# KegWasher_1_8_LogicIO_Schematic.net
KiCad netlist of a schematic drawn in EasyEDA
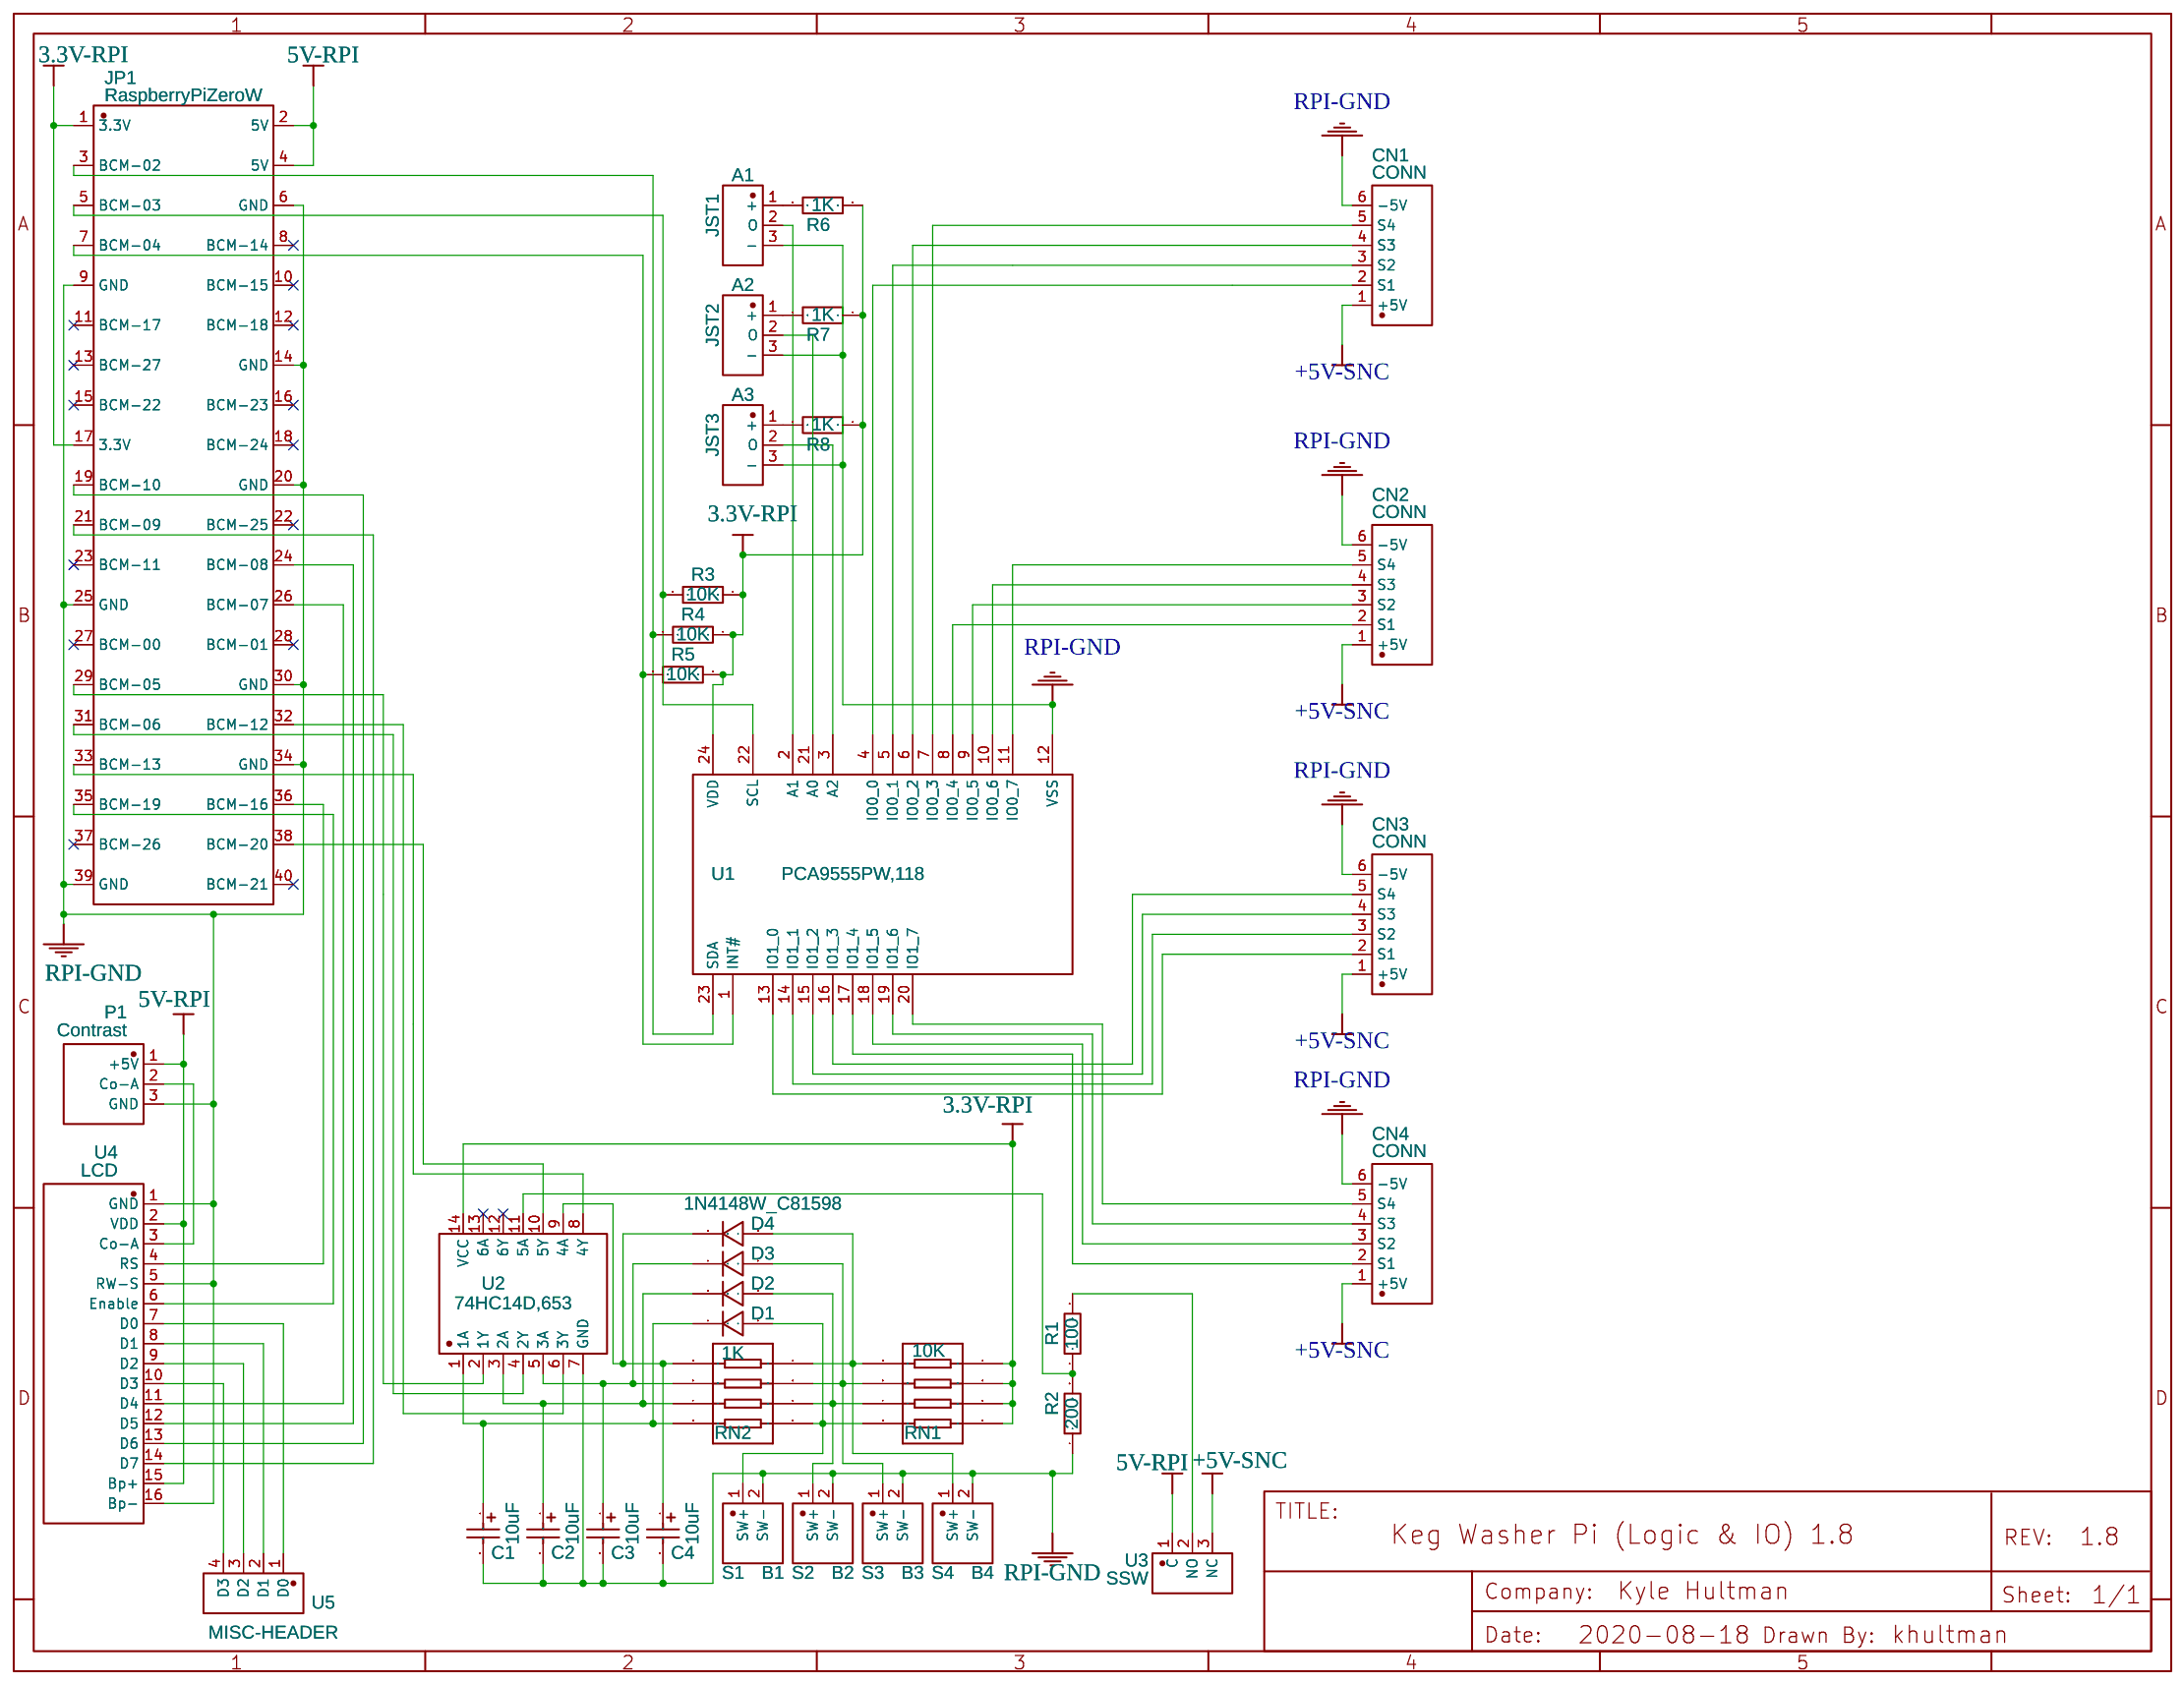
[diagram p0: schematic sheet]

(export (version "E")
  (design (tool "Eeschema 10.0.6"))
  (components
    (comp (ref "C1")
      (value "10uF")
      (fields
        (field (name "BOM_Manufacturer Part") "TAJA106K016RNJ")
        (field (name "BOM_Supplier Part") "C7171")
      )
      (libsource (lib "") (part "TAJA106K016RNJ"))
    )
    (comp (ref "C2")
      (value "10uF")
      (fields
        (field (name "BOM_Manufacturer Part") "TAJA106K016RNJ")
        (field (name "BOM_Supplier Part") "C7171")
      )
      (libsource (lib "") (part "TAJA106K016RNJ"))
    )
    (comp (ref "C3")
      (value "10uF")
      (fields
        (field (name "BOM_Manufacturer Part") "TAJA106K016RNJ")
        (field (name "BOM_Supplier Part") "C7171")
      )
      (libsource (lib "") (part "TAJA106K016RNJ"))
    )
    (comp (ref "C4")
      (value "10uF")
      (fields
        (field (name "BOM_Manufacturer Part") "TAJA106K016RNJ")
        (field (name "BOM_Supplier Part") "C7171")
      )
      (libsource (lib "") (part "TAJA106K016RNJ"))
    )
    (comp (ref "CN1") (value "CONN") (libsource (lib "") (part "CONN")))
    (comp (ref "CN2") (value "CONN") (libsource (lib "") (part "CONN")))
    (comp (ref "CN3") (value "CONN") (libsource (lib "") (part "CONN")))
    (comp (ref "CN4") (value "CONN") (libsource (lib "") (part "CONN")))
    (comp (ref "D1")
      (value "1N4148W_C81598")
      (fields (field (name "BOM_Manufacturer Part") "1N4148W") (field (name "BOM_Supplier Part") "C81598"))
      (libsource (lib "") (part "1N4148W_C81598"))
    )
    (comp (ref "D2")
      (value "1N4148W_C81598")
      (fields (field (name "BOM_Manufacturer Part") "1N4148W") (field (name "BOM_Supplier Part") "C81598"))
      (libsource (lib "") (part "1N4148W_C81598"))
    )
    (comp (ref "D3")
      (value "1N4148W_C81598")
      (fields (field (name "BOM_Manufacturer Part") "1N4148W") (field (name "BOM_Supplier Part") "C81598"))
      (libsource (lib "") (part "1N4148W_C81598"))
    )
    (comp (ref "D4")
      (value "1N4148W_C81598")
      (fields (field (name "BOM_Manufacturer Part") "1N4148W") (field (name "BOM_Supplier Part") "C81598"))
      (libsource (lib "") (part "1N4148W_C81598"))
    )
    (comp (ref "JP1") (value "RaspberryPiZeroW") (libsource (lib "") (part "RaspberryPiZeroW")))
    (comp (ref "JST1") (value "A1") (libsource (lib "") (part "JST1")))
    (comp (ref "JST2") (value "A2") (libsource (lib "") (part "JST1")))
    (comp (ref "JST3") (value "A3") (libsource (lib "") (part "JST1")))
    (comp (ref "P1") (value "Contrast") (libsource (lib "") (part "Contrast")))
    (comp (ref "R1")
      (value "100")
      (fields
        (field (name "BOM_Manufacturer Part") "1206W4F1000T5E")
        (field (name "BOM_Supplier Part") "C17901")
      )
      (libsource (lib "") (part "1206W4F1000T5E"))
    )
    (comp (ref "R2")
      (value "200")
      (fields
        (field (name "BOM_Manufacturer Part") "0603WAF2000T5E")
        (field (name "BOM_Supplier Part") "C8218")
      )
      (libsource (lib "") (part "0603WAF2000T5E"))
    )
    (comp (ref "R3")
      (value "10K")
      (fields
        (field (name "BOM_Manufacturer Part") "1206W4F1002T5E")
        (field (name "BOM_Supplier Part") "C17902")
      )
      (libsource (lib "") (part "1206W4F1002T5E"))
    )
    (comp (ref "R4")
      (value "10K")
      (fields
        (field (name "BOM_Manufacturer Part") "1206W4F1002T5E")
        (field (name "BOM_Supplier Part") "C17902")
      )
      (libsource (lib "") (part "1206W4F1002T5E"))
    )
    (comp (ref "R5")
      (value "10K")
      (fields
        (field (name "BOM_Manufacturer Part") "1206W4F1002T5E")
        (field (name "BOM_Supplier Part") "C17902")
      )
      (libsource (lib "") (part "1206W4F1002T5E"))
    )
    (comp (ref "R6")
      (value "1K")
      (fields
        (field (name "BOM_Manufacturer Part") "0805W8F1001T5E")
        (field (name "BOM_Supplier Part") "C17513")
      )
      (libsource (lib "") (part "0805W8F1001T5E"))
    )
    (comp (ref "R7")
      (value "1K")
      (fields
        (field (name "BOM_Manufacturer Part") "0805W8F1001T5E")
        (field (name "BOM_Supplier Part") "C17513")
      )
      (libsource (lib "") (part "0805W8F1001T5E"))
    )
    (comp (ref "R8")
      (value "1K")
      (fields
        (field (name "BOM_Manufacturer Part") "0805W8F1001T5E")
        (field (name "BOM_Supplier Part") "C17513")
      )
      (libsource (lib "") (part "0805W8F1001T5E"))
    )
    (comp (ref "RN1")
      (value "10K")
      (fields
        (field (name "BOM_Manufacturer Part") "4D02WGJ0103TCE")
        (field (name "BOM_Supplier Part") "C25725")
      )
      (libsource (lib "") (part "4D02WGJ0103TCE"))
    )
    (comp (ref "RN2")
      (value "1K")
      (fields
        (field (name "BOM_Manufacturer Part") "4D02WGJ0102TCE")
        (field (name "BOM_Supplier Part") "C25726")
      )
      (libsource (lib "") (part "4D02WGJ0102TCE"))
    )
    (comp (ref "S1") (value "B1") (libsource (lib "") (part "SW")))
    (comp (ref "S2") (value "B2") (libsource (lib "") (part "SW")))
    (comp (ref "S3") (value "B3") (libsource (lib "") (part "SW")))
    (comp (ref "S4") (value "B4") (libsource (lib "") (part "SW")))
    (comp (ref "U1")
      (value "PCA9555PW,118")
      (fields (field (name "BOM_Supplier Part") "C128392"))
      (libsource (lib "") (part "PCA9555PW,118"))
    )
    (comp (ref "U2")
      (value "74HC14D,653")
      (fields (field (name "BOM_Supplier Part") "C5605"))
      (libsource (lib "") (part "74HC14D,653"))
    )
    (comp (ref "U3") (value "SSW") (libsource (lib "") (part "SSW")))
    (comp (ref "U4") (value "LCD") (libsource (lib "") (part "LCD")))
    (comp (ref "U5") (value "MISC-HEADER") (libsource (lib "") (part "MISC-HEADER")))
  )
  (nets
    (net (code "1") (name "+5V-SNC") (class "Default")
      (node (ref "CN1") (pin "1") (pinfunction "+5V_1") (pintype "unspecified"))
      (node (ref "CN2") (pin "1") (pinfunction "+5V_1") (pintype "unspecified"))
      (node (ref "CN3") (pin "1") (pinfunction "+5V_1") (pintype "unspecified"))
      (node (ref "CN4") (pin "1") (pinfunction "+5V_1") (pintype "unspecified"))
      (node (ref "U3") (pin "3") (pinfunction "NC_3") (pintype "unspecified"))
    )
    (net (code "2") (name "3.3V-RPI") (class "Default")
      (node (ref "JP1") (pin "1") (pinfunction "3.3V_1") (pintype "unspecified"))
      (node (ref "JP1") (pin "17") (pinfunction "3.3V_17") (pintype "unspecified"))
      (node (ref "R3") (pin "1") (pinfunction "1_1") (pintype "input"))
      (node (ref "R4") (pin "1") (pinfunction "1_1") (pintype "input"))
      (node (ref "R5") (pin "1") (pinfunction "1_1") (pintype "input"))
      (node (ref "R6") (pin "1") (pinfunction "1_1") (pintype "input"))
      (node (ref "R7") (pin "1") (pinfunction "1_1") (pintype "input"))
      (node (ref "R8") (pin "1") (pinfunction "1_1") (pintype "input"))
      (node (ref "RN1") (pin "1") (pinfunction "1_1") (pintype "input"))
      (node (ref "RN1") (pin "2") (pinfunction "2_2") (pintype "input"))
      (node (ref "RN1") (pin "3") (pinfunction "3_3") (pintype "input"))
      (node (ref "RN1") (pin "4") (pinfunction "4_4") (pintype "input"))
      (node (ref "U1") (pin "24") (pinfunction "VDD_24") (pintype "passive"))
      (node (ref "U2") (pin "14") (pinfunction "VCC_14") (pintype "unspecified"))
    )
    (net (code "3") (name "5V-RPI") (class "Default")
      (node (ref "JP1") (pin "2") (pinfunction "5V_2") (pintype "unspecified"))
      (node (ref "JP1") (pin "4") (pinfunction "5V_4") (pintype "unspecified"))
      (node (ref "P1") (pin "1") (pinfunction "+5V_1") (pintype "unspecified"))
      (node (ref "U3") (pin "1") (pinfunction "C_1") (pintype "unspecified"))
      (node (ref "U4") (pin "15") (pinfunction "Bp+_15") (pintype "unspecified"))
      (node (ref "U4") (pin "2") (pinfunction "VDD_2") (pintype "unspecified"))
    )
    (net (code "4") (name "Net-(CN1-S1)") (class "Default")
      (node (ref "CN1") (pin "2") (pinfunction "S1_2") (pintype "unspecified"))
      (node (ref "U1") (pin "4") (pinfunction "IO0_0_4") (pintype "unspecified"))
    )
    (net (code "5") (name "Net-(CN1-S2)") (class "Default")
      (node (ref "CN1") (pin "3") (pinfunction "S2_3") (pintype "unspecified"))
      (node (ref "U1") (pin "5") (pinfunction "IO0_1_5") (pintype "unspecified"))
    )
    (net (code "6") (name "Net-(CN1-S3)") (class "Default")
      (node (ref "CN1") (pin "4") (pinfunction "S3_4") (pintype "unspecified"))
      (node (ref "U1") (pin "6") (pinfunction "IO0_2_6") (pintype "unspecified"))
    )
    (net (code "7") (name "Net-(CN1-S4)") (class "Default")
      (node (ref "CN1") (pin "5") (pinfunction "S4_5") (pintype "unspecified"))
      (node (ref "U1") (pin "7") (pinfunction "IO0_3_7") (pintype "unspecified"))
    )
    (net (code "8") (name "Net-(CN2-S1)") (class "Default")
      (node (ref "CN2") (pin "2") (pinfunction "S1_2") (pintype "unspecified"))
      (node (ref "U1") (pin "8") (pinfunction "IO0_4_8") (pintype "unspecified"))
    )
    (net (code "9") (name "Net-(CN2-S2)") (class "Default")
      (node (ref "CN2") (pin "3") (pinfunction "S2_3") (pintype "unspecified"))
      (node (ref "U1") (pin "9") (pinfunction "IO0_5_9") (pintype "unspecified"))
    )
    (net (code "10") (name "Net-(CN2-S3)") (class "Default")
      (node (ref "CN2") (pin "4") (pinfunction "S3_4") (pintype "unspecified"))
      (node (ref "U1") (pin "10") (pinfunction "IO0_6_10") (pintype "unspecified"))
    )
    (net (code "11") (name "Net-(CN2-S4)") (class "Default")
      (node (ref "CN2") (pin "5") (pinfunction "S4_5") (pintype "unspecified"))
      (node (ref "U1") (pin "11") (pinfunction "IO0_7_11") (pintype "unspecified"))
    )
    (net (code "12") (name "Net-(CN3-S1)") (class "Default")
      (node (ref "CN3") (pin "2") (pinfunction "S1_2") (pintype "unspecified"))
      (node (ref "U1") (pin "13") (pinfunction "IO1_0_13") (pintype "unspecified"))
    )
    (net (code "13") (name "Net-(CN3-S2)") (class "Default")
      (node (ref "CN3") (pin "3") (pinfunction "S2_3") (pintype "unspecified"))
      (node (ref "U1") (pin "14") (pinfunction "IO1_1_14") (pintype "unspecified"))
    )
    (net (code "14") (name "Net-(CN3-S3)") (class "Default")
      (node (ref "CN3") (pin "4") (pinfunction "S3_4") (pintype "unspecified"))
      (node (ref "U1") (pin "15") (pinfunction "IO1_2_15") (pintype "unspecified"))
    )
    (net (code "15") (name "Net-(CN3-S4)") (class "Default")
      (node (ref "CN3") (pin "5") (pinfunction "S4_5") (pintype "unspecified"))
      (node (ref "U1") (pin "16") (pinfunction "IO1_3_16") (pintype "unspecified"))
    )
    (net (code "16") (name "Net-(CN4-S1)") (class "Default")
      (node (ref "CN4") (pin "2") (pinfunction "S1_2") (pintype "unspecified"))
      (node (ref "U1") (pin "17") (pinfunction "IO1_4_17") (pintype "unspecified"))
    )
    (net (code "17") (name "Net-(CN4-S2)") (class "Default")
      (node (ref "CN4") (pin "3") (pinfunction "S2_3") (pintype "unspecified"))
      (node (ref "U1") (pin "18") (pinfunction "IO1_5_18") (pintype "unspecified"))
    )
    (net (code "18") (name "Net-(CN4-S3)") (class "Default")
      (node (ref "CN4") (pin "4") (pinfunction "S3_4") (pintype "unspecified"))
      (node (ref "U1") (pin "19") (pinfunction "IO1_6_19") (pintype "unspecified"))
    )
    (net (code "19") (name "Net-(CN4-S4)") (class "Default")
      (node (ref "CN4") (pin "5") (pinfunction "S4_5") (pintype "unspecified"))
      (node (ref "U1") (pin "20") (pinfunction "IO1_7_20") (pintype "unspecified"))
    )
    (net (code "20") (name "Net-(D1-A)") (class "Default")
      (node (ref "D1") (pin "2") (pinfunction "A_2") (pintype "unspecified"))
      (node (ref "RN1") (pin "8") (pinfunction "8_8") (pintype "input"))
      (node (ref "RN2") (pin "1") (pinfunction "1_1") (pintype "input"))
      (node (ref "S1") (pin "1") (pinfunction "SW+_1") (pintype "unspecified"))
    )
    (net (code "21") (name "Net-(D1-K)") (class "Default")
      (node (ref "C1") (pin "1") (pinfunction "1_1") (pintype "input"))
      (node (ref "D1") (pin "1") (pinfunction "K_1") (pintype "unspecified"))
      (node (ref "RN2") (pin "8") (pinfunction "8_8") (pintype "input"))
      (node (ref "U2") (pin "1") (pinfunction "1A_1") (pintype "unspecified"))
    )
    (net (code "22") (name "Net-(D2-A)") (class "Default")
      (node (ref "D2") (pin "2") (pinfunction "A_2") (pintype "unspecified"))
      (node (ref "RN1") (pin "7") (pinfunction "7_7") (pintype "input"))
      (node (ref "RN2") (pin "2") (pinfunction "2_2") (pintype "input"))
      (node (ref "S2") (pin "1") (pinfunction "SW+_1") (pintype "unspecified"))
    )
    (net (code "23") (name "Net-(D2-K)") (class "Default")
      (node (ref "C2") (pin "1") (pinfunction "1_1") (pintype "input"))
      (node (ref "D2") (pin "1") (pinfunction "K_1") (pintype "unspecified"))
      (node (ref "RN2") (pin "7") (pinfunction "7_7") (pintype "input"))
      (node (ref "U2") (pin "3") (pinfunction "2A_3") (pintype "unspecified"))
    )
    (net (code "24") (name "Net-(D3-A)") (class "Default")
      (node (ref "D3") (pin "2") (pinfunction "A_2") (pintype "unspecified"))
      (node (ref "RN1") (pin "6") (pinfunction "6_6") (pintype "input"))
      (node (ref "RN2") (pin "3") (pinfunction "3_3") (pintype "input"))
      (node (ref "S3") (pin "1") (pinfunction "SW+_1") (pintype "unspecified"))
    )
    (net (code "25") (name "Net-(D3-K)") (class "Default")
      (node (ref "C3") (pin "1") (pinfunction "1_1") (pintype "input"))
      (node (ref "D3") (pin "1") (pinfunction "K_1") (pintype "unspecified"))
      (node (ref "RN2") (pin "6") (pinfunction "6_6") (pintype "input"))
      (node (ref "U2") (pin "5") (pinfunction "3A_5") (pintype "unspecified"))
    )
    (net (code "26") (name "Net-(D4-A)") (class "Default")
      (node (ref "D4") (pin "2") (pinfunction "A_2") (pintype "unspecified"))
      (node (ref "RN1") (pin "5") (pinfunction "5_5") (pintype "input"))
      (node (ref "RN2") (pin "4") (pinfunction "4_4") (pintype "input"))
      (node (ref "S4") (pin "1") (pinfunction "SW+_1") (pintype "unspecified"))
    )
    (net (code "27") (name "Net-(D4-K)") (class "Default")
      (node (ref "C4") (pin "1") (pinfunction "1_1") (pintype "input"))
      (node (ref "D4") (pin "1") (pinfunction "K_1") (pintype "unspecified"))
      (node (ref "RN2") (pin "5") (pinfunction "5_5") (pintype "input"))
      (node (ref "U2") (pin "9") (pinfunction "4A_9") (pintype "unspecified"))
    )
    (net (code "28") (name "Net-(JP1-BCM-02)") (class "Default")
      (node (ref "JP1") (pin "3") (pinfunction "BCM-02_3") (pintype "unspecified"))
      (node (ref "R4") (pin "2") (pinfunction "2_2") (pintype "input"))
      (node (ref "U1") (pin "23") (pinfunction "SDA_23") (pintype "unspecified"))
    )
    (net (code "29") (name "Net-(JP1-BCM-03)") (class "Default")
      (node (ref "JP1") (pin "5") (pinfunction "BCM-03_5") (pintype "unspecified"))
      (node (ref "R3") (pin "2") (pinfunction "2_2") (pintype "input"))
      (node (ref "U1") (pin "22") (pinfunction "SCL_22") (pintype "input"))
    )
    (net (code "30") (name "Net-(JP1-BCM-04)") (class "Default")
      (node (ref "JP1") (pin "7") (pinfunction "BCM-04_7") (pintype "unspecified"))
      (node (ref "R5") (pin "2") (pinfunction "2_2") (pintype "input"))
      (node (ref "U1") (pin "1") (pinfunction "INT#_1") (pintype "output"))
    )
    (net (code "31") (name "Net-(JP1-BCM-05)") (class "Default")
      (node (ref "JP1") (pin "29") (pinfunction "BCM-05_29") (pintype "unspecified"))
      (node (ref "U2") (pin "2") (pinfunction "1Y_2") (pintype "unspecified"))
    )
    (net (code "32") (name "Net-(JP1-BCM-06)") (class "Default")
      (node (ref "JP1") (pin "31") (pinfunction "BCM-06_31") (pintype "unspecified"))
      (node (ref "U2") (pin "4") (pinfunction "2Y_4") (pintype "unspecified"))
    )
    (net (code "33") (name "Net-(JP1-BCM-07)") (class "Default")
      (node (ref "JP1") (pin "26") (pinfunction "BCM-07_26") (pintype "unspecified"))
      (node (ref "U4") (pin "11") (pinfunction "D4_11") (pintype "unspecified"))
    )
    (net (code "34") (name "Net-(JP1-BCM-08)") (class "Default")
      (node (ref "JP1") (pin "24") (pinfunction "BCM-08_24") (pintype "unspecified"))
      (node (ref "U4") (pin "12") (pinfunction "D5_12") (pintype "unspecified"))
    )
    (net (code "35") (name "Net-(JP1-BCM-09)") (class "Default")
      (node (ref "JP1") (pin "21") (pinfunction "BCM-09_21") (pintype "unspecified"))
      (node (ref "U4") (pin "14") (pinfunction "D7_14") (pintype "unspecified"))
    )
    (net (code "36") (name "Net-(JP1-BCM-10)") (class "Default")
      (node (ref "JP1") (pin "19") (pinfunction "BCM-10_19") (pintype "unspecified"))
      (node (ref "U4") (pin "13") (pinfunction "D6_13") (pintype "unspecified"))
    )
    (net (code "37") (name "Net-(JP1-BCM-12)") (class "Default")
      (node (ref "JP1") (pin "32") (pinfunction "BCM-12_32") (pintype "unspecified"))
      (node (ref "U2") (pin "6") (pinfunction "3Y_6") (pintype "unspecified"))
    )
    (net (code "38") (name "Net-(JP1-BCM-13)") (class "Default")
      (node (ref "JP1") (pin "33") (pinfunction "BCM-13_33") (pintype "unspecified"))
      (node (ref "U2") (pin "8") (pinfunction "4Y_8") (pintype "unspecified"))
    )
    (net (code "39") (name "Net-(JP1-BCM-16)") (class "Default")
      (node (ref "JP1") (pin "36") (pinfunction "BCM-16_36") (pintype "unspecified"))
      (node (ref "U4") (pin "4") (pinfunction "RS_4") (pintype "unspecified"))
    )
    (net (code "40") (name "Net-(JP1-BCM-19)") (class "Default")
      (node (ref "JP1") (pin "35") (pinfunction "BCM-19_35") (pintype "unspecified"))
      (node (ref "U4") (pin "6") (pinfunction "Enable_6") (pintype "unspecified"))
    )
    (net (code "41") (name "Net-(JP1-BCM-20)") (class "Default")
      (node (ref "JP1") (pin "38") (pinfunction "BCM-20_38") (pintype "unspecified"))
      (node (ref "U2") (pin "10") (pinfunction "5Y_10") (pintype "unspecified"))
    )
    (net (code "42") (name "Net-(JST1-+)") (class "Default")
      (node (ref "JST1") (pin "1") (pinfunction "+_1") (pintype "unspecified"))
      (node (ref "R6") (pin "2") (pinfunction "2_2") (pintype "input"))
    )
    (net (code "43") (name "Net-(JST1-O)") (class "Default")
      (node (ref "JST1") (pin "2") (pinfunction "O_2") (pintype "unspecified"))
      (node (ref "U1") (pin "2") (pinfunction "A1_2") (pintype "input"))
    )
    (net (code "44") (name "Net-(JST2-+)") (class "Default")
      (node (ref "JST2") (pin "1") (pinfunction "+_1") (pintype "unspecified"))
      (node (ref "R7") (pin "2") (pinfunction "2_2") (pintype "input"))
    )
    (net (code "45") (name "Net-(JST2-O)") (class "Default")
      (node (ref "JST2") (pin "2") (pinfunction "O_2") (pintype "unspecified"))
      (node (ref "U1") (pin "21") (pinfunction "A0_21") (pintype "input"))
    )
    (net (code "46") (name "Net-(JST3-+)") (class "Default")
      (node (ref "JST3") (pin "1") (pinfunction "+_1") (pintype "unspecified"))
      (node (ref "R8") (pin "2") (pinfunction "2_2") (pintype "input"))
    )
    (net (code "47") (name "Net-(JST3-O)") (class "Default")
      (node (ref "JST3") (pin "2") (pinfunction "O_2") (pintype "unspecified"))
      (node (ref "U1") (pin "3") (pinfunction "A2_3") (pintype "input"))
    )
    (net (code "48") (name "Net-(P1-Co-A)") (class "Default")
      (node (ref "P1") (pin "2") (pinfunction "Co-A_2") (pintype "unspecified"))
      (node (ref "U4") (pin "3") (pinfunction "Co-A_3") (pintype "unspecified"))
    )
    (net (code "49") (name "Net-(U2-5A)") (class "Default")
      (node (ref "R1") (pin "1") (pinfunction "1_1") (pintype "input"))
      (node (ref "R2") (pin "2") (pinfunction "2_2") (pintype "input"))
      (node (ref "U2") (pin "11") (pinfunction "5A_11") (pintype "unspecified"))
    )
    (net (code "50") (name "Net-(U3-NO)") (class "Default")
      (node (ref "R1") (pin "2") (pinfunction "2_2") (pintype "input"))
      (node (ref "U3") (pin "2") (pinfunction "NO_2") (pintype "unspecified"))
    )
    (net (code "51") (name "Net-(U4-D0)") (class "Default")
      (node (ref "U4") (pin "7") (pinfunction "D0_7") (pintype "unspecified"))
      (node (ref "U5") (pin "1") (pinfunction "D0_1") (pintype "unspecified"))
    )
    (net (code "52") (name "Net-(U4-D1)") (class "Default")
      (node (ref "U4") (pin "8") (pinfunction "D1_8") (pintype "unspecified"))
      (node (ref "U5") (pin "2") (pinfunction "D1_2") (pintype "unspecified"))
    )
    (net (code "53") (name "Net-(U4-D2)") (class "Default")
      (node (ref "U4") (pin "9") (pinfunction "D2_9") (pintype "unspecified"))
      (node (ref "U5") (pin "3") (pinfunction "D2_3") (pintype "unspecified"))
    )
    (net (code "54") (name "Net-(U4-D3)") (class "Default")
      (node (ref "U4") (pin "10") (pinfunction "D3_10") (pintype "unspecified"))
      (node (ref "U5") (pin "4") (pinfunction "D3_4") (pintype "unspecified"))
    )
    (net (code "55") (name "RPI-GND") (class "Default")
      (node (ref "C1") (pin "2") (pinfunction "2_2") (pintype "input"))
      (node (ref "C2") (pin "2") (pinfunction "2_2") (pintype "input"))
      (node (ref "C3") (pin "2") (pinfunction "2_2") (pintype "input"))
      (node (ref "C4") (pin "2") (pinfunction "2_2") (pintype "input"))
      (node (ref "CN1") (pin "6") (pinfunction "-5V_6") (pintype "unspecified"))
      (node (ref "CN2") (pin "6") (pinfunction "-5V_6") (pintype "unspecified"))
      (node (ref "CN3") (pin "6") (pinfunction "-5V_6") (pintype "unspecified"))
      (node (ref "CN4") (pin "6") (pinfunction "-5V_6") (pintype "unspecified"))
      (node (ref "JP1") (pin "14") (pinfunction "GND_14") (pintype "unspecified"))
      (node (ref "JP1") (pin "20") (pinfunction "GND_20") (pintype "unspecified"))
      (node (ref "JP1") (pin "25") (pinfunction "GND_25") (pintype "unspecified"))
      (node (ref "JP1") (pin "30") (pinfunction "GND_30") (pintype "unspecified"))
      (node (ref "JP1") (pin "34") (pinfunction "GND_34") (pintype "unspecified"))
      (node (ref "JP1") (pin "39") (pinfunction "GND_39") (pintype "unspecified"))
      (node (ref "JP1") (pin "6") (pinfunction "GND_6") (pintype "unspecified"))
      (node (ref "JP1") (pin "9") (pinfunction "GND_9") (pintype "unspecified"))
      (node (ref "JST1") (pin "3") (pinfunction "-_3") (pintype "unspecified"))
      (node (ref "JST2") (pin "3") (pinfunction "-_3") (pintype "unspecified"))
      (node (ref "JST3") (pin "3") (pinfunction "-_3") (pintype "unspecified"))
      (node (ref "P1") (pin "3") (pinfunction "GND_3") (pintype "unspecified"))
      (node (ref "R2") (pin "1") (pinfunction "1_1") (pintype "input"))
      (node (ref "S1") (pin "2") (pinfunction "SW-_2") (pintype "unspecified"))
      (node (ref "S2") (pin "2") (pinfunction "SW-_2") (pintype "unspecified"))
      (node (ref "S3") (pin "2") (pinfunction "SW-_2") (pintype "unspecified"))
      (node (ref "S4") (pin "2") (pinfunction "SW-_2") (pintype "unspecified"))
      (node (ref "U1") (pin "12") (pinfunction "VSS_12") (pintype "unspecified"))
      (node (ref "U2") (pin "7") (pinfunction "GND_7") (pintype "unspecified"))
      (node (ref "U4") (pin "1") (pinfunction "GND_1") (pintype "unspecified"))
      (node (ref "U4") (pin "16") (pinfunction "Bp-_16") (pintype "unspecified"))
      (node (ref "U4") (pin "5") (pinfunction "RW-S_5") (pintype "unspecified"))
    )
    (net (code "56") (name "unconnected-(JP1-BCM-00-Pad27)") (class "Default")
      (node (ref "JP1") (pin "27") (pinfunction "BCM-00_27") (pintype "unspecified+no_connect"))
    )
    (net (code "57") (name "unconnected-(JP1-BCM-01-Pad28)") (class "Default")
      (node (ref "JP1") (pin "28") (pinfunction "BCM-01_28") (pintype "unspecified+no_connect"))
    )
    (net (code "58") (name "unconnected-(JP1-BCM-11-Pad23)") (class "Default")
      (node (ref "JP1") (pin "23") (pinfunction "BCM-11_23") (pintype "unspecified+no_connect"))
    )
    (net (code "59") (name "unconnected-(JP1-BCM-14-Pad8)") (class "Default")
      (node (ref "JP1") (pin "8") (pinfunction "BCM-14_8") (pintype "unspecified+no_connect"))
    )
    (net (code "60") (name "unconnected-(JP1-BCM-15-Pad10)") (class "Default")
      (node (ref "JP1") (pin "10") (pinfunction "BCM-15_10") (pintype "unspecified+no_connect"))
    )
    (net (code "61") (name "unconnected-(JP1-BCM-17-Pad11)") (class "Default")
      (node (ref "JP1") (pin "11") (pinfunction "BCM-17_11") (pintype "unspecified+no_connect"))
    )
    (net (code "62") (name "unconnected-(JP1-BCM-18-Pad12)") (class "Default")
      (node (ref "JP1") (pin "12") (pinfunction "BCM-18_12") (pintype "unspecified+no_connect"))
    )
    (net (code "63") (name "unconnected-(JP1-BCM-21-Pad40)") (class "Default")
      (node (ref "JP1") (pin "40") (pinfunction "BCM-21_40") (pintype "unspecified+no_connect"))
    )
    (net (code "64") (name "unconnected-(JP1-BCM-22-Pad15)") (class "Default")
      (node (ref "JP1") (pin "15") (pinfunction "BCM-22_15") (pintype "unspecified+no_connect"))
    )
    (net (code "65") (name "unconnected-(JP1-BCM-23-Pad16)") (class "Default")
      (node (ref "JP1") (pin "16") (pinfunction "BCM-23_16") (pintype "unspecified+no_connect"))
    )
    (net (code "66") (name "unconnected-(JP1-BCM-24-Pad18)") (class "Default")
      (node (ref "JP1") (pin "18") (pinfunction "BCM-24_18") (pintype "unspecified+no_connect"))
    )
    (net (code "67") (name "unconnected-(JP1-BCM-25-Pad22)") (class "Default")
      (node (ref "JP1") (pin "22") (pinfunction "BCM-25_22") (pintype "unspecified+no_connect"))
    )
    (net (code "68") (name "unconnected-(JP1-BCM-26-Pad37)") (class "Default")
      (node (ref "JP1") (pin "37") (pinfunction "BCM-26_37") (pintype "unspecified+no_connect"))
    )
    (net (code "69") (name "unconnected-(JP1-BCM-27-Pad13)") (class "Default")
      (node (ref "JP1") (pin "13") (pinfunction "BCM-27_13") (pintype "unspecified+no_connect"))
    )
    (net (code "70") (name "unconnected-(U2-6A-Pad13)") (class "Default")
      (node (ref "U2") (pin "13") (pinfunction "6A_13") (pintype "unspecified+no_connect"))
    )
    (net (code "71") (name "unconnected-(U2-6Y-Pad12)") (class "Default")
      (node (ref "U2") (pin "12") (pinfunction "6Y_12") (pintype "unspecified+no_connect"))
    )
  )
)
